# HID.net
KiCad netlist of a schematic drawn in EAGLE
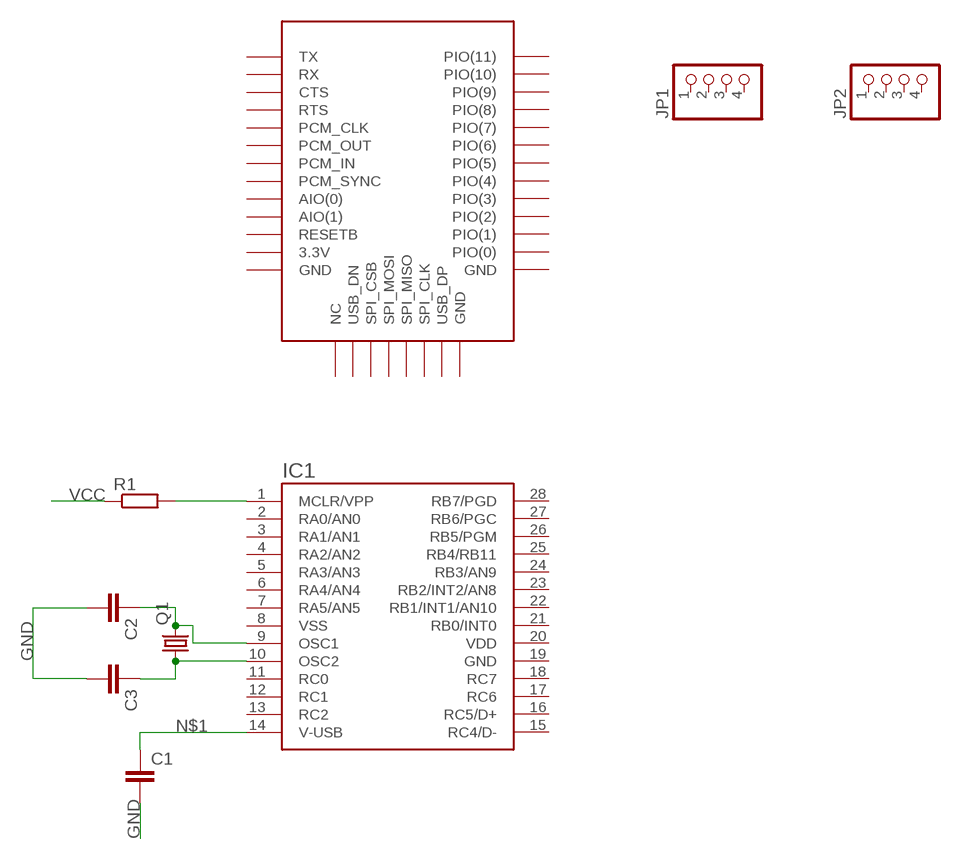
[diagram p0: schematic, sheet 1]

(export (version "E")
  (design (tool "Eeschema 10.0.6"))
  (components
    (comp (ref "C1")
      (value "C2.5/5")
      (footprint "eagle-import:C2.5-5")
      (libsource (lib "eagle-import") (part "C2.5/5"))
    )
    (comp (ref "C2")
      (value "C2.5/2")
      (footprint "eagle-import:C2.5-2")
      (libsource (lib "eagle-import") (part "C2.5/2"))
    )
    (comp (ref "C3")
      (value "C2.5/2")
      (footprint "eagle-import:C2.5-2")
      (libsource (lib "eagle-import") (part "C2.5/2"))
    )
    (comp (ref "IC1")
      (value "PIC18F2550SMD-28")
      (footprint "eagle-import:SO28")
      (libsource (lib "eagle-import") (part "PIC18F2550SMD-28"))
    )
    (comp (ref "IC2")
      (value "BC04_BLUETOOTH")
      (footprint "eagle-import:BC04")
      (libsource (lib "eagle-import") (part "BC04_BLUETOOTH"))
    )
    (comp (ref "JP1")
      (value "PINHD-1X4")
      (footprint "eagle-import:1X04")
      (libsource (lib "eagle-import") (part "PINHD-1X4"))
    )
    (comp (ref "JP2")
      (value "PINHD-1X4")
      (footprint "eagle-import:1X04")
      (libsource (lib "eagle-import") (part "PINHD-1X4"))
    )
    (comp (ref "Q1")
      (value "CRYSTALHC49U-V")
      (footprint "eagle-import:HC49U-V")
      (libsource (lib "eagle-import") (part "CRYSTALHC49U-V"))
    )
    (comp (ref "R1")
      (value "R-EU_0207/10")
      (footprint "eagle-import:0207_10")
      (libsource (lib "eagle-import") (part "R-EU_0207/10"))
    )
  )
  (nets
    (net (code "1") (name "/GND") (class "Default")
      (node (ref "C1") (pin "2") (pinfunction "2_2") (pintype "passive"))
      (node (ref "C2") (pin "2") (pinfunction "2_2") (pintype "passive"))
      (node (ref "C3") (pin "2") (pinfunction "2_2") (pintype "passive"))
    )
    (net (code "2") (name "/N$1") (class "Default")
      (node (ref "C1") (pin "1") (pinfunction "1_1") (pintype "passive"))
      (node (ref "IC1") (pin "14") (pinfunction "V-USB_14") (pintype "bidirectional"))
    )
    (net (code "3") (name "/VCC") (class "Default")
      (node (ref "R1") (pin "1") (pinfunction "1_1") (pintype "passive"))
    )
    (net (code "4") (name "Net-(IC1-MCLR{slash}VPP)") (class "Default")
      (node (ref "IC1") (pin "1") (pinfunction "MCLR/VPP_1") (pintype "bidirectional"))
      (node (ref "R1") (pin "2") (pinfunction "2_2") (pintype "passive"))
    )
    (net (code "5") (name "Net-(IC1-OSC1)") (class "Default")
      (node (ref "C2") (pin "1") (pinfunction "1_1") (pintype "passive"))
      (node (ref "IC1") (pin "9") (pinfunction "OSC1_9") (pintype "bidirectional"))
      (node (ref "Q1") (pin "2") (pinfunction "2_2") (pintype "passive"))
    )
    (net (code "6") (name "Net-(IC1-OSC2)") (class "Default")
      (node (ref "C3") (pin "1") (pinfunction "1_1") (pintype "passive"))
      (node (ref "IC1") (pin "10") (pinfunction "OSC2_10") (pintype "bidirectional"))
      (node (ref "Q1") (pin "1") (pinfunction "1_1") (pintype "passive"))
    )
    (net (code "7") (name "unconnected-(IC1-GND-Pad19)") (class "Default")
      (node (ref "IC1") (pin "19") (pinfunction "GND_19") (pintype "bidirectional"))
    )
    (net (code "8") (name "unconnected-(IC1-RA0{slash}AN0-Pad2)") (class "Default")
      (node (ref "IC1") (pin "2") (pinfunction "RA0/AN0_2") (pintype "bidirectional"))
    )
    (net (code "9") (name "unconnected-(IC1-RA1{slash}AN1-Pad3)") (class "Default")
      (node (ref "IC1") (pin "3") (pinfunction "RA1/AN1_3") (pintype "bidirectional"))
    )
    (net (code "10") (name "unconnected-(IC1-RA2{slash}AN2-Pad4)") (class "Default")
      (node (ref "IC1") (pin "4") (pinfunction "RA2/AN2_4") (pintype "bidirectional"))
    )
    (net (code "11") (name "unconnected-(IC1-RA3{slash}AN3-Pad5)") (class "Default")
      (node (ref "IC1") (pin "5") (pinfunction "RA3/AN3_5") (pintype "bidirectional"))
    )
    (net (code "12") (name "unconnected-(IC1-RA4{slash}AN4-Pad6)") (class "Default")
      (node (ref "IC1") (pin "6") (pinfunction "RA4/AN4_6") (pintype "bidirectional"))
    )
    (net (code "13") (name "unconnected-(IC1-RA5{slash}AN5-Pad7)") (class "Default")
      (node (ref "IC1") (pin "7") (pinfunction "RA5/AN5_7") (pintype "bidirectional"))
    )
    (net (code "14") (name "unconnected-(IC1-RB0{slash}INT0-Pad21)") (class "Default")
      (node (ref "IC1") (pin "21") (pinfunction "RB0/INT0_21") (pintype "bidirectional"))
    )
    (net (code "15") (name "unconnected-(IC1-RB1{slash}INT1{slash}AN10-Pad22)") (class "Default")
      (node (ref "IC1") (pin "22") (pinfunction "RB1/INT1/AN10_22") (pintype "bidirectional"))
    )
    (net (code "16") (name "unconnected-(IC1-RB2{slash}INT2{slash}AN8-Pad23)") (class "Default")
      (node (ref "IC1") (pin "23") (pinfunction "RB2/INT2/AN8_23") (pintype "bidirectional"))
    )
    (net (code "17") (name "unconnected-(IC1-RB3{slash}AN9-Pad24)") (class "Default")
      (node (ref "IC1") (pin "24") (pinfunction "RB3/AN9_24") (pintype "bidirectional"))
    )
    (net (code "18") (name "unconnected-(IC1-RB4{slash}RB11-Pad25)") (class "Default")
      (node (ref "IC1") (pin "25") (pinfunction "RB4/RB11_25") (pintype "bidirectional"))
    )
    (net (code "19") (name "unconnected-(IC1-RB5{slash}PGM-Pad26)") (class "Default")
      (node (ref "IC1") (pin "26") (pinfunction "RB5/PGM_26") (pintype "bidirectional"))
    )
    (net (code "20") (name "unconnected-(IC1-RB6{slash}PGC-Pad27)") (class "Default")
      (node (ref "IC1") (pin "27") (pinfunction "RB6/PGC_27") (pintype "bidirectional"))
    )
    (net (code "21") (name "unconnected-(IC1-RB7{slash}PGD-Pad28)") (class "Default")
      (node (ref "IC1") (pin "28") (pinfunction "RB7/PGD_28") (pintype "bidirectional"))
    )
    (net (code "22") (name "unconnected-(IC1-RC0-Pad11)") (class "Default")
      (node (ref "IC1") (pin "11") (pinfunction "RC0_11") (pintype "bidirectional"))
    )
    (net (code "23") (name "unconnected-(IC1-RC1-Pad12)") (class "Default")
      (node (ref "IC1") (pin "12") (pinfunction "RC1_12") (pintype "bidirectional"))
    )
    (net (code "24") (name "unconnected-(IC1-RC2-Pad13)") (class "Default")
      (node (ref "IC1") (pin "13") (pinfunction "RC2_13") (pintype "bidirectional"))
    )
    (net (code "25") (name "unconnected-(IC1-RC4{slash}D--Pad15)") (class "Default")
      (node (ref "IC1") (pin "15") (pinfunction "RC4/D-_15") (pintype "bidirectional"))
    )
    (net (code "26") (name "unconnected-(IC1-RC5{slash}D+-Pad16)") (class "Default")
      (node (ref "IC1") (pin "16") (pinfunction "RC5/D+_16") (pintype "bidirectional"))
    )
    (net (code "27") (name "unconnected-(IC1-RC6-Pad17)") (class "Default")
      (node (ref "IC1") (pin "17") (pinfunction "RC6_17") (pintype "bidirectional"))
    )
    (net (code "28") (name "unconnected-(IC1-RC7-Pad18)") (class "Default")
      (node (ref "IC1") (pin "18") (pinfunction "RC7_18") (pintype "bidirectional"))
    )
    (net (code "29") (name "unconnected-(IC1-VDD-Pad20)") (class "Default")
      (node (ref "IC1") (pin "20") (pinfunction "VDD_20") (pintype "bidirectional"))
    )
    (net (code "30") (name "unconnected-(IC1-VSS-Pad8)") (class "Default")
      (node (ref "IC1") (pin "8") (pinfunction "VSS_8") (pintype "bidirectional"))
    )
    (net (code "31") (name "unconnected-(IC2-3.3V-PadP$12)") (class "Default")
      (node (ref "IC2") (pin "P$12") (pinfunction "3.3V_P$12") (pintype "bidirectional"))
    )
    (net (code "32") (name "unconnected-(IC2-AIO(0)-PadP$9)") (class "Default")
      (node (ref "IC2") (pin "P$9") (pinfunction "AIO(0)_P$9") (pintype "bidirectional"))
    )
    (net (code "33") (name "unconnected-(IC2-AIO(1)-PadP$10)") (class "Default")
      (node (ref "IC2") (pin "P$10") (pinfunction "AIO(1)_P$10") (pintype "bidirectional"))
    )
    (net (code "34") (name "unconnected-(IC2-CTS-PadP$3)") (class "Default")
      (node (ref "IC2") (pin "P$3") (pinfunction "CTS_P$3") (pintype "bidirectional"))
    )
    (net (code "35") (name "unconnected-(IC2-GND-PadP$13)") (class "Default")
      (node (ref "IC2") (pin "P$13") (pinfunction "GND_P$13") (pintype "bidirectional"))
    )
    (net (code "36") (name "unconnected-(IC2-GND-PadP$21)") (class "Default")
      (node (ref "IC2") (pin "P$21") (pinfunction "GND_P$21") (pintype "bidirectional"))
    )
    (net (code "37") (name "unconnected-(IC2-GND-PadP$22)") (class "Default")
      (node (ref "IC2") (pin "P$22") (pinfunction "GND_P$22") (pintype "bidirectional"))
    )
    (net (code "38") (name "unconnected-(IC2-NC-PadP$14)") (class "Default")
      (node (ref "IC2") (pin "P$14") (pinfunction "NC_P$14") (pintype "bidirectional"))
    )
    (net (code "39") (name "unconnected-(IC2-PCM_CLK-PadP$5)") (class "Default")
      (node (ref "IC2") (pin "P$5") (pinfunction "PCM_CLK_P$5") (pintype "bidirectional"))
    )
    (net (code "40") (name "unconnected-(IC2-PCM_IN-PadP$7)") (class "Default")
      (node (ref "IC2") (pin "P$7") (pinfunction "PCM_IN_P$7") (pintype "bidirectional"))
    )
    (net (code "41") (name "unconnected-(IC2-PCM_OUT-PadP$6)") (class "Default")
      (node (ref "IC2") (pin "P$6") (pinfunction "PCM_OUT_P$6") (pintype "bidirectional"))
    )
    (net (code "42") (name "unconnected-(IC2-PCM_SYNC-PadP$8)") (class "Default")
      (node (ref "IC2") (pin "P$8") (pinfunction "PCM_SYNC_P$8") (pintype "bidirectional"))
    )
    (net (code "43") (name "unconnected-(IC2-PIO(0)-PadP$23)") (class "Default")
      (node (ref "IC2") (pin "P$23") (pinfunction "PIO(0)_P$23") (pintype "bidirectional"))
    )
    (net (code "44") (name "unconnected-(IC2-PIO(1)-PadP$24)") (class "Default")
      (node (ref "IC2") (pin "P$24") (pinfunction "PIO(1)_P$24") (pintype "bidirectional"))
    )
    (net (code "45") (name "unconnected-(IC2-PIO(2)-PadP$25)") (class "Default")
      (node (ref "IC2") (pin "P$25") (pinfunction "PIO(2)_P$25") (pintype "bidirectional"))
    )
    (net (code "46") (name "unconnected-(IC2-PIO(3)-PadP$26)") (class "Default")
      (node (ref "IC2") (pin "P$26") (pinfunction "PIO(3)_P$26") (pintype "bidirectional"))
    )
    (net (code "47") (name "unconnected-(IC2-PIO(4)-PadP$27)") (class "Default")
      (node (ref "IC2") (pin "P$27") (pinfunction "PIO(4)_P$27") (pintype "bidirectional"))
    )
    (net (code "48") (name "unconnected-(IC2-PIO(5)-PadP$28)") (class "Default")
      (node (ref "IC2") (pin "P$28") (pinfunction "PIO(5)_P$28") (pintype "bidirectional"))
    )
    (net (code "49") (name "unconnected-(IC2-PIO(6)-PadP$29)") (class "Default")
      (node (ref "IC2") (pin "P$29") (pinfunction "PIO(6)_P$29") (pintype "bidirectional"))
    )
    (net (code "50") (name "unconnected-(IC2-PIO(7)-PadP$30)") (class "Default")
      (node (ref "IC2") (pin "P$30") (pinfunction "PIO(7)_P$30") (pintype "bidirectional"))
    )
    (net (code "51") (name "unconnected-(IC2-PIO(8)-PadP$31)") (class "Default")
      (node (ref "IC2") (pin "P$31") (pinfunction "PIO(8)_P$31") (pintype "bidirectional"))
    )
    (net (code "52") (name "unconnected-(IC2-PIO(9)-PadP$32)") (class "Default")
      (node (ref "IC2") (pin "P$32") (pinfunction "PIO(9)_P$32") (pintype "bidirectional"))
    )
    (net (code "53") (name "unconnected-(IC2-PIO(10)-PadP$33)") (class "Default")
      (node (ref "IC2") (pin "P$33") (pinfunction "PIO(10)_P$33") (pintype "bidirectional"))
    )
    (net (code "54") (name "unconnected-(IC2-PIO(11)-PadP$34)") (class "Default")
      (node (ref "IC2") (pin "P$34") (pinfunction "PIO(11)_P$34") (pintype "bidirectional"))
    )
    (net (code "55") (name "unconnected-(IC2-RESETB-PadP$11)") (class "Default")
      (node (ref "IC2") (pin "P$11") (pinfunction "RESETB_P$11") (pintype "bidirectional"))
    )
    (net (code "56") (name "unconnected-(IC2-RTS-PadP$4)") (class "Default")
      (node (ref "IC2") (pin "P$4") (pinfunction "RTS_P$4") (pintype "bidirectional"))
    )
    (net (code "57") (name "unconnected-(IC2-RX-PadP$2)") (class "Default")
      (node (ref "IC2") (pin "P$2") (pinfunction "RX_P$2") (pintype "bidirectional"))
    )
    (net (code "58") (name "unconnected-(IC2-SPI_CLK-PadP$19)") (class "Default")
      (node (ref "IC2") (pin "P$19") (pinfunction "SPI_CLK_P$19") (pintype "bidirectional"))
    )
    (net (code "59") (name "unconnected-(IC2-SPI_CSB-PadP$16)") (class "Default")
      (node (ref "IC2") (pin "P$16") (pinfunction "SPI_CSB_P$16") (pintype "bidirectional"))
    )
    (net (code "60") (name "unconnected-(IC2-SPI_MISO-PadP$18)") (class "Default")
      (node (ref "IC2") (pin "P$18") (pinfunction "SPI_MISO_P$18") (pintype "bidirectional"))
    )
    (net (code "61") (name "unconnected-(IC2-SPI_MOSI-PadP$17)") (class "Default")
      (node (ref "IC2") (pin "P$17") (pinfunction "SPI_MOSI_P$17") (pintype "bidirectional"))
    )
    (net (code "62") (name "unconnected-(IC2-TX-PadP$1)") (class "Default")
      (node (ref "IC2") (pin "P$1") (pinfunction "TX_P$1") (pintype "bidirectional"))
    )
    (net (code "63") (name "unconnected-(IC2-USB_DN-PadP$15)") (class "Default")
      (node (ref "IC2") (pin "P$15") (pinfunction "USB_DN_P$15") (pintype "bidirectional"))
    )
    (net (code "64") (name "unconnected-(IC2-USB_DP-PadP$20)") (class "Default")
      (node (ref "IC2") (pin "P$20") (pinfunction "USB_DP_P$20") (pintype "bidirectional"))
    )
    (net (code "65") (name "unconnected-(JP1-Pad1)") (class "Default")
      (node (ref "JP1") (pin "1") (pinfunction "1_1") (pintype "passive"))
    )
    (net (code "66") (name "unconnected-(JP1-Pad2)") (class "Default")
      (node (ref "JP1") (pin "2") (pinfunction "2_2") (pintype "passive"))
    )
    (net (code "67") (name "unconnected-(JP1-Pad3)") (class "Default")
      (node (ref "JP1") (pin "3") (pinfunction "3_3") (pintype "passive"))
    )
    (net (code "68") (name "unconnected-(JP1-Pad4)") (class "Default")
      (node (ref "JP1") (pin "4") (pinfunction "4_4") (pintype "passive"))
    )
    (net (code "69") (name "unconnected-(JP2-Pad1)") (class "Default")
      (node (ref "JP2") (pin "1") (pinfunction "1_1") (pintype "passive"))
    )
    (net (code "70") (name "unconnected-(JP2-Pad2)") (class "Default")
      (node (ref "JP2") (pin "2") (pinfunction "2_2") (pintype "passive"))
    )
    (net (code "71") (name "unconnected-(JP2-Pad3)") (class "Default")
      (node (ref "JP2") (pin "3") (pinfunction "3_3") (pintype "passive"))
    )
    (net (code "72") (name "unconnected-(JP2-Pad4)") (class "Default")
      (node (ref "JP2") (pin "4") (pinfunction "4_4") (pintype "passive"))
    )
  )
)
